# Attenuator.net
KiCad netlist of a schematic drawn in Altium Designer
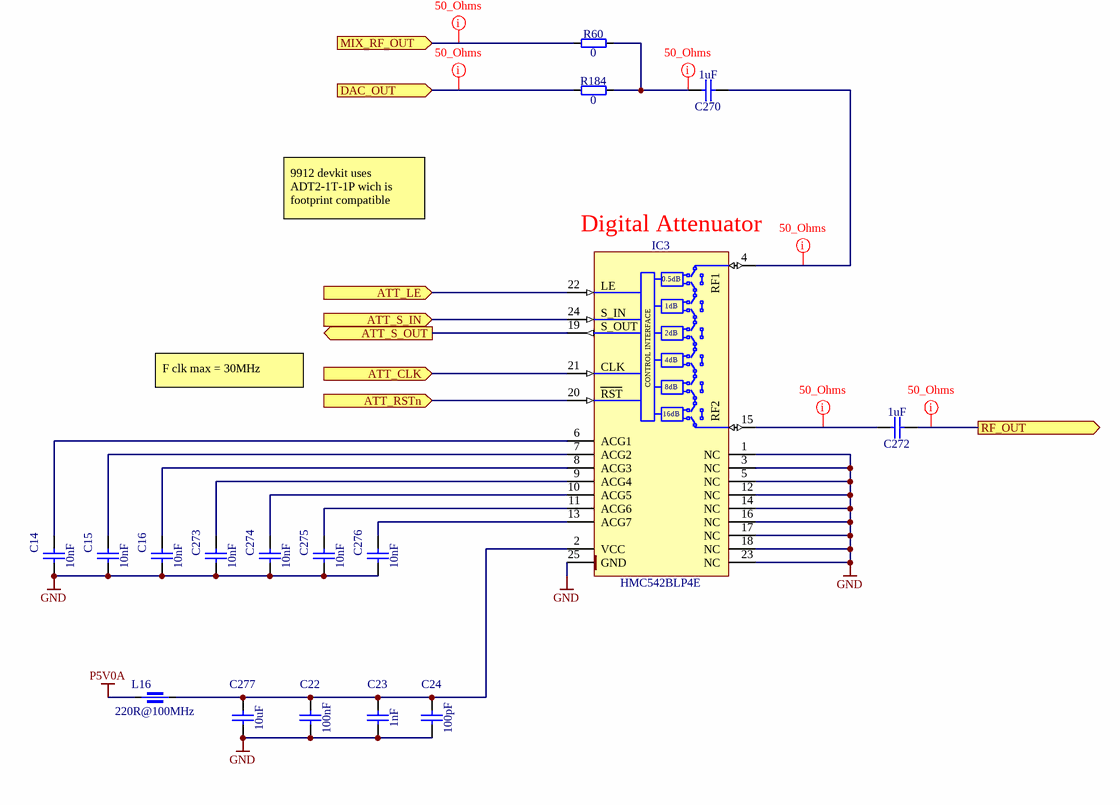
[diagram p0: Attenuator.SchDoc]

(export (version "E")
  (design (tool "Eeschema 10.0.6"))
  (components
    (comp (ref "C14")
      (value "10nF")
      (footprint "CAPC1005X55N")
      (description "Non-polarised capacitor")
      (fields
        (field (name "PART NUMBER") "CC0402_10NF_16V_10%_X7R")
        (field (name "VOLTAGE") "16V")
        (field (name "AUTHOR") "CERN DEM JLC")
      )
      (libsource (lib "Capacitors") (part "Capacitor - non polarized"))
    )
    (comp (ref "C15")
      (value "10nF")
      (footprint "CAPC1005X55N")
      (description "Non-polarised capacitor")
      (fields
        (field (name "PART NUMBER") "CC0402_10NF_16V_10%_X7R")
        (field (name "VOLTAGE") "16V")
        (field (name "AUTHOR") "CERN DEM JLC")
      )
      (libsource (lib "Capacitors") (part "Capacitor - non polarized"))
    )
    (comp (ref "C16")
      (value "10nF")
      (footprint "CAPC1005X55N")
      (description "Non-polarised capacitor")
      (fields
        (field (name "PART NUMBER") "CC0402_10NF_16V_10%_X7R")
        (field (name "VOLTAGE") "16V")
        (field (name "AUTHOR") "CERN DEM JLC")
      )
      (libsource (lib "Capacitors") (part "Capacitor - non polarized"))
    )
    (comp (ref "C22")
      (value "100nF")
      (footprint "CAPC1005X55N")
      (description "Non-polarised capacitor")
      (fields
        (field (name "PART NUMBER") "CC0402_100NF_16V_10%_X7R")
        (field (name "VOLTAGE") "16V")
        (field (name "AUTHOR") "CERN DEM JLC")
      )
      (libsource (lib "Capacitors") (part "Capacitor - non polarized"))
    )
    (comp (ref "C23")
      (value "1nF")
      (footprint "CAPC1005X55N")
      (description "Non-polarised capacitor")
      (fields
        (field (name "PART NUMBER") "CC0402_1NF_50V_10%_X7R")
        (field (name "VOLTAGE") "50V")
        (field (name "AUTHOR") "CERN DEM JLC")
      )
      (libsource (lib "Capacitors") (part "Capacitor - non polarized"))
    )
    (comp (ref "C24")
      (value "100pF")
      (footprint "CAPC1005X55N")
      (description "Non-polarised capacitor")
      (fields
        (field (name "PART NUMBER") "CC0402_100PF_50V_5%_C0G")
        (field (name "VOLTAGE") "50V")
        (field (name "AUTHOR") "CERN DEM JLC")
      )
      (libsource (lib "Capacitors") (part "Capacitor - non polarized"))
    )
    (comp (ref "C270")
      (value "1uF")
      (footprint "CAPC1005X55N")
      (description "Non-polarised capacitor")
      (fields
        (field (name "PART NUMBER") "CC0402_1UF_16V_10%_X5R")
        (field (name "VOLTAGE") "16V")
        (field (name "AUTHOR") "CERN DEM JLC")
      )
      (libsource (lib "Capacitors") (part "Capacitor - non polarized"))
    )
    (comp (ref "C272")
      (value "1uF")
      (footprint "CAPC1005X55N")
      (description "Non-polarised capacitor")
      (fields
        (field (name "PART NUMBER") "CC0402_1UF_16V_10%_X5R")
        (field (name "VOLTAGE") "16V")
        (field (name "AUTHOR") "CERN DEM JLC")
      )
      (libsource (lib "Capacitors") (part "Capacitor - non polarized"))
    )
    (comp (ref "C273")
      (value "10nF")
      (footprint "CAPC1005X55N")
      (description "Non-polarised capacitor")
      (fields
        (field (name "PART NUMBER") "CC0402_10NF_16V_10%_X7R")
        (field (name "VOLTAGE") "16V")
        (field (name "AUTHOR") "CERN DEM JLC")
      )
      (libsource (lib "Capacitors") (part "Capacitor - non polarized"))
    )
    (comp (ref "C274")
      (value "10nF")
      (footprint "CAPC1005X55N")
      (description "Non-polarised capacitor")
      (fields
        (field (name "PART NUMBER") "CC0402_10NF_16V_10%_X7R")
        (field (name "VOLTAGE") "16V")
        (field (name "AUTHOR") "CERN DEM JLC")
      )
      (libsource (lib "Capacitors") (part "Capacitor - non polarized"))
    )
    (comp (ref "C275")
      (value "10nF")
      (footprint "CAPC1005X55N")
      (description "Non-polarised capacitor")
      (fields
        (field (name "PART NUMBER") "CC0402_10NF_16V_10%_X7R")
        (field (name "VOLTAGE") "16V")
        (field (name "AUTHOR") "CERN DEM JLC")
      )
      (libsource (lib "Capacitors") (part "Capacitor - non polarized"))
    )
    (comp (ref "C276")
      (value "10nF")
      (footprint "CAPC1005X55N")
      (description "Non-polarised capacitor")
      (fields
        (field (name "PART NUMBER") "CC0402_10NF_16V_10%_X7R")
        (field (name "VOLTAGE") "16V")
        (field (name "AUTHOR") "CERN DEM JLC")
      )
      (libsource (lib "Capacitors") (part "Capacitor - non polarized"))
    )
    (comp (ref "C277")
      (value "10uF")
      (footprint "CAPC1608X80N")
      (description "Non-polarised capacitor")
      (fields
        (field (name "PART NUMBER") "CC0603_10UF_16V_20%_X5R")
        (field (name "VOLTAGE") "16V")
        (field (name "AUTHOR") "CERN DEM MR")
      )
      (libsource (lib "Capacitors") (part "Capacitor - non polarized"))
    )
    (comp (ref "IC3")
      (value "HMC542BLP4E")
      (footprint "QFN50P400X400X100-25N-S295")
      (description "0.5dB LSB GaAs MMIC 6-bit Digital Serial Control Attenuator, DC - 4GHz")
      (fields (field (name "MANUFACTURER") "HITTITE MICROWAVE CORP") (field (name "AUTHOR") "CERN DEM JMW"))
      (libsource (lib "ICs And Semiconductors") (part "HMC542BLP4E"))
    )
    (comp (ref "L16")
      (value "220R@100MHz")
      (footprint "INDC1608X95N")
      (fields
        (field (name "PART NUMBER") "IND0603_MURATA_BLM18SG221TN1")
        (field (name "POWER") "2.5A")
        (field (name "TOLERANCE") "±25%")
        (field (name "AUTHOR") "CERN DEM MR")
      )
      (libsource (lib "Inductors & Transformers") (part "Ferrite Bead"))
    )
    (comp (ref "R60")
      (value "0")
      (footprint "RESC1005X40N")
      (description "Resistor")
      (fields
        (field (name "PART NUMBER") "R0402_0R_JUMPER")
        (field (name "MANUFACTURER") "GENERIC")
        (field (name "AUTHOR") "CERN DEM JLC")
      )
      (libsource (lib "Resistors") (part "Resistor"))
    )
    (comp (ref "R184")
      (value "0")
      (footprint "RESC1005X40N")
      (description "Resistor")
      (fields
        (field (name "PART NUMBER") "R0402_0R_JUMPER")
        (field (name "MANUFACTURER") "GENERIC")
        (field (name "AUTHOR") "CERN DEM JLC")
      )
      (libsource (lib "Resistors") (part "Resistor"))
    )
  )
  (nets
    (net (code "1") (name "/ATT_CLK") (class "Default")
      (node (ref "IC3") (pin "21") (pinfunction "SHIFT_CLOCK_21") (pintype "input"))
    )
    (net (code "2") (name "/ATT_LE") (class "Default")
      (node (ref "IC3") (pin "22") (pinfunction "LATCH_ENABLE_22") (pintype "input"))
    )
    (net (code "3") (name "/ATT_RSTn") (class "Default")
      (node (ref "IC3") (pin "20") (pinfunction "~{RESET}_20") (pintype "input"))
    )
    (net (code "4") (name "/ATT_S_IN") (class "Default")
      (node (ref "IC3") (pin "24") (pinfunction "SERIAL_INPUT_24") (pintype "input"))
    )
    (net (code "5") (name "/ATT_S_OUT") (class "Default")
      (node (ref "IC3") (pin "19") (pinfunction "SERIAL_OUTPUT_19") (pintype "output"))
    )
    (net (code "6") (name "/DAC_OUT") (class "Default")
      (node (ref "R184") (pin "1") (pinfunction "1_1") (pintype "passive"))
    )
    (net (code "7") (name "/MIX_RF_OUT") (class "Default")
      (node (ref "R60") (pin "1") (pinfunction "1_1") (pintype "passive"))
    )
    (net (code "8") (name "/RF_OUT") (class "Default")
      (node (ref "C272") (pin "1") (pinfunction "1_1") (pintype "passive"))
    )
    (net (code "9") (name "GND") (class "Default")
      (node (ref "C14") (pin "1") (pinfunction "1_1") (pintype "passive"))
      (node (ref "C15") (pin "1") (pinfunction "1_1") (pintype "passive"))
      (node (ref "C16") (pin "1") (pinfunction "1_1") (pintype "passive"))
      (node (ref "C22") (pin "1") (pinfunction "1_1") (pintype "passive"))
      (node (ref "C23") (pin "1") (pinfunction "1_1") (pintype "passive"))
      (node (ref "C24") (pin "1") (pinfunction "1_1") (pintype "passive"))
      (node (ref "C273") (pin "1") (pinfunction "1_1") (pintype "passive"))
      (node (ref "C274") (pin "1") (pinfunction "1_1") (pintype "passive"))
      (node (ref "C275") (pin "1") (pinfunction "1_1") (pintype "passive"))
      (node (ref "C276") (pin "1") (pinfunction "1_1") (pintype "passive"))
      (node (ref "C277") (pin "1") (pinfunction "1_1") (pintype "passive"))
      (node (ref "IC3") (pin "1") (pinfunction "NC_1") (pintype "passive"))
      (node (ref "IC3") (pin "12") (pinfunction "NC_12") (pintype "passive"))
      (node (ref "IC3") (pin "14") (pinfunction "NC_14") (pintype "passive"))
      (node (ref "IC3") (pin "16") (pinfunction "NC_16") (pintype "passive"))
      (node (ref "IC3") (pin "17") (pinfunction "NC_17") (pintype "passive"))
      (node (ref "IC3") (pin "18") (pinfunction "NC_18") (pintype "passive"))
      (node (ref "IC3") (pin "23") (pinfunction "NC_23") (pintype "passive"))
      (node (ref "IC3") (pin "25") (pinfunction "GND_25") (pintype "power_in"))
      (node (ref "IC3") (pin "3") (pinfunction "NC_3") (pintype "passive"))
      (node (ref "IC3") (pin "5") (pinfunction "NC_5") (pintype "passive"))
    )
    (net (code "10") (name "Net-(C270-Pad2)") (class "Default")
      (node (ref "C270") (pin "2") (pinfunction "2_2") (pintype "passive"))
      (node (ref "R184") (pin "2") (pinfunction "2_2") (pintype "passive"))
      (node (ref "R60") (pin "2") (pinfunction "2_2") (pintype "passive"))
    )
    (net (code "11") (name "Net-(IC3-ACG1)") (class "Default")
      (node (ref "C14") (pin "2") (pinfunction "2_2") (pintype "passive"))
      (node (ref "IC3") (pin "6") (pinfunction "ACG1_6") (pintype "passive"))
    )
    (net (code "12") (name "Net-(IC3-ACG2)") (class "Default")
      (node (ref "C15") (pin "2") (pinfunction "2_2") (pintype "passive"))
      (node (ref "IC3") (pin "7") (pinfunction "ACG2_7") (pintype "passive"))
    )
    (net (code "13") (name "Net-(IC3-ACG3)") (class "Default")
      (node (ref "C16") (pin "2") (pinfunction "2_2") (pintype "passive"))
      (node (ref "IC3") (pin "8") (pinfunction "ACG3_8") (pintype "passive"))
    )
    (net (code "14") (name "Net-(IC3-ACG4)") (class "Default")
      (node (ref "C273") (pin "2") (pinfunction "2_2") (pintype "passive"))
      (node (ref "IC3") (pin "9") (pinfunction "ACG4_9") (pintype "passive"))
    )
    (net (code "15") (name "Net-(IC3-ACG5)") (class "Default")
      (node (ref "C274") (pin "2") (pinfunction "2_2") (pintype "passive"))
      (node (ref "IC3") (pin "10") (pinfunction "ACG5_10") (pintype "passive"))
    )
    (net (code "16") (name "Net-(IC3-ACG6)") (class "Default")
      (node (ref "C275") (pin "2") (pinfunction "2_2") (pintype "passive"))
      (node (ref "IC3") (pin "11") (pinfunction "ACG6_11") (pintype "passive"))
    )
    (net (code "17") (name "Net-(IC3-ACG7)") (class "Default")
      (node (ref "C276") (pin "2") (pinfunction "2_2") (pintype "passive"))
      (node (ref "IC3") (pin "13") (pinfunction "ACG7_13") (pintype "passive"))
    )
    (net (code "18") (name "Net-(IC3-RF1)") (class "Default")
      (node (ref "C270") (pin "1") (pinfunction "1_1") (pintype "passive"))
      (node (ref "IC3") (pin "4") (pinfunction "RF1_4") (pintype "bidirectional"))
    )
    (net (code "19") (name "Net-(IC3-RF2)") (class "Default")
      (node (ref "C272") (pin "2") (pinfunction "2_2") (pintype "passive"))
      (node (ref "IC3") (pin "15") (pinfunction "RF2_15") (pintype "bidirectional"))
    )
    (net (code "20") (name "Net-(IC3-VCC)") (class "Default")
      (node (ref "C22") (pin "2") (pinfunction "2_2") (pintype "passive"))
      (node (ref "C23") (pin "2") (pinfunction "2_2") (pintype "passive"))
      (node (ref "C24") (pin "2") (pinfunction "2_2") (pintype "passive"))
      (node (ref "C277") (pin "2") (pinfunction "2_2") (pintype "passive"))
      (node (ref "IC3") (pin "2") (pinfunction "VCC_2") (pintype "power_in"))
      (node (ref "L16") (pin "2") (pinfunction "2_2") (pintype "passive"))
    )
    (net (code "21") (name "P5V0A") (class "Default")
      (node (ref "L16") (pin "1") (pinfunction "1_1") (pintype "passive"))
    )
  )
)
